# 1-8.net
KiCad netlist of a schematic drawn in EAGLE
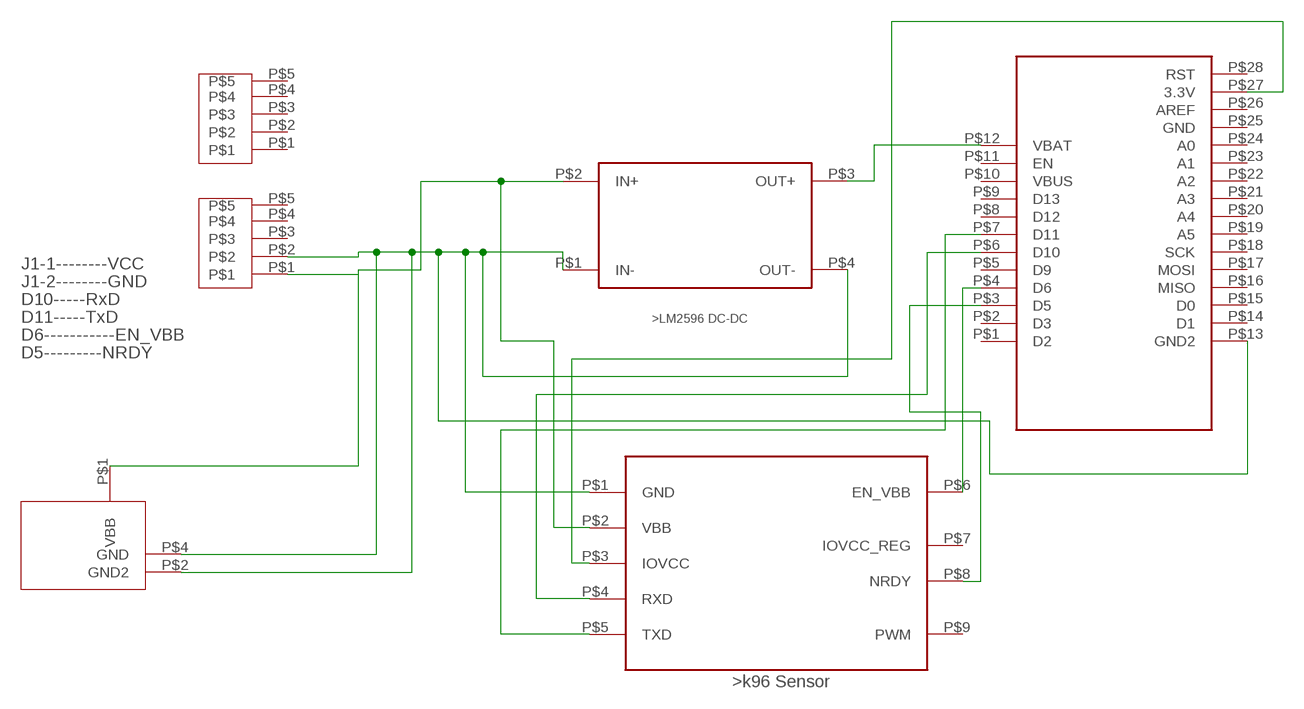
[diagram p0: schematic, sheet 1]

(export (version "E")
  (design (tool "Eeschema 10.0.6"))
  (components
    (comp (ref "DCDC1")
      (value "DCDC")
      (footprint "eagle-import:DCDC")
      (libsource (lib "eagle-import") (part "DCDC"))
    )
    (comp (ref "FEATHER1")
      (value "FEATHER")
      (footprint "eagle-import:FEATHER")
      (libsource (lib "eagle-import") (part "FEATHER"))
    )
    (comp (ref "K96SENSOR1")
      (value "K96SENSOR")
      (footprint "eagle-import:K96SENSOR")
      (libsource (lib "eagle-import") (part "K96SENSOR"))
    )
    (comp (ref "PIN1")
      (value "PIN")
      (footprint "eagle-import:PIN")
      (libsource (lib "eagle-import") (part "PIN"))
    )
    (comp (ref "PIN2")
      (value "PIN")
      (footprint "eagle-import:PIN")
      (libsource (lib "eagle-import") (part "PIN"))
    )
    (comp (ref "U$1")
      (value "POWER")
      (footprint "eagle-import:POWERIN")
      (libsource (lib "eagle-import") (part "POWER"))
    )
  )
  (nets
    (net (code "1") (name "Net-(DCDC1-IN+)") (class "Default")
      (node (ref "DCDC1") (pin "P$2") (pinfunction "IN+_P$2") (pintype "bidirectional"))
      (node (ref "K96SENSOR1") (pin "P$2") (pinfunction "VBB_P$2") (pintype "bidirectional"))
      (node (ref "PIN2") (pin "P$1") (pinfunction "P$1_P$1") (pintype "bidirectional"))
      (node (ref "U$1") (pin "P$1") (pinfunction "VBB_P$1") (pintype "bidirectional"))
    )
    (net (code "2") (name "Net-(DCDC1-IN-)") (class "Default")
      (node (ref "DCDC1") (pin "P$1") (pinfunction "IN-_P$1") (pintype "bidirectional"))
      (node (ref "DCDC1") (pin "P$4") (pinfunction "OUT-_P$4") (pintype "bidirectional"))
      (node (ref "FEATHER1") (pin "P$13") (pinfunction "GND2_P$13") (pintype "bidirectional"))
      (node (ref "K96SENSOR1") (pin "P$1") (pinfunction "GND_P$1") (pintype "bidirectional"))
      (node (ref "PIN2") (pin "P$2") (pinfunction "P$2_P$2") (pintype "bidirectional"))
      (node (ref "U$1") (pin "P$2") (pinfunction "GND2_P$2") (pintype "bidirectional"))
      (node (ref "U$1") (pin "P$4") (pinfunction "GND_P$4") (pintype "bidirectional"))
    )
    (net (code "3") (name "Net-(DCDC1-OUT+)") (class "Default")
      (node (ref "DCDC1") (pin "P$3") (pinfunction "OUT+_P$3") (pintype "bidirectional"))
      (node (ref "FEATHER1") (pin "P$12") (pinfunction "VBAT_P$12") (pintype "bidirectional"))
    )
    (net (code "4") (name "Net-(FEATHER1-3.3V)") (class "Default")
      (node (ref "FEATHER1") (pin "P$27") (pinfunction "3.3V_P$27") (pintype "bidirectional"))
      (node (ref "K96SENSOR1") (pin "P$3") (pinfunction "IOVCC_P$3") (pintype "bidirectional"))
    )
    (net (code "5") (name "Net-(FEATHER1-D5)") (class "Default")
      (node (ref "FEATHER1") (pin "P$3") (pinfunction "D5_P$3") (pintype "bidirectional"))
      (node (ref "K96SENSOR1") (pin "P$8") (pinfunction "NRDY_P$8") (pintype "bidirectional"))
    )
    (net (code "6") (name "Net-(FEATHER1-D6)") (class "Default")
      (node (ref "FEATHER1") (pin "P$4") (pinfunction "D6_P$4") (pintype "bidirectional"))
      (node (ref "K96SENSOR1") (pin "P$6") (pinfunction "EN_VBB_P$6") (pintype "bidirectional"))
    )
    (net (code "7") (name "Net-(FEATHER1-D10)") (class "Default")
      (node (ref "FEATHER1") (pin "P$6") (pinfunction "D10_P$6") (pintype "bidirectional"))
      (node (ref "K96SENSOR1") (pin "P$4") (pinfunction "RXD_P$4") (pintype "bidirectional"))
    )
    (net (code "8") (name "Net-(FEATHER1-D11)") (class "Default")
      (node (ref "FEATHER1") (pin "P$7") (pinfunction "D11_P$7") (pintype "bidirectional"))
      (node (ref "K96SENSOR1") (pin "P$5") (pinfunction "TXD_P$5") (pintype "bidirectional"))
    )
    (net (code "9") (name "unconnected-(FEATHER1-A0-PadP$24)") (class "Default")
      (node (ref "FEATHER1") (pin "P$24") (pinfunction "A0_P$24") (pintype "bidirectional"))
    )
    (net (code "10") (name "unconnected-(FEATHER1-A1-PadP$23)") (class "Default")
      (node (ref "FEATHER1") (pin "P$23") (pinfunction "A1_P$23") (pintype "bidirectional"))
    )
    (net (code "11") (name "unconnected-(FEATHER1-A2-PadP$22)") (class "Default")
      (node (ref "FEATHER1") (pin "P$22") (pinfunction "A2_P$22") (pintype "bidirectional"))
    )
    (net (code "12") (name "unconnected-(FEATHER1-A3-PadP$21)") (class "Default")
      (node (ref "FEATHER1") (pin "P$21") (pinfunction "A3_P$21") (pintype "bidirectional"))
    )
    (net (code "13") (name "unconnected-(FEATHER1-A4-PadP$20)") (class "Default")
      (node (ref "FEATHER1") (pin "P$20") (pinfunction "A4_P$20") (pintype "bidirectional"))
    )
    (net (code "14") (name "unconnected-(FEATHER1-A5-PadP$19)") (class "Default")
      (node (ref "FEATHER1") (pin "P$19") (pinfunction "A5_P$19") (pintype "bidirectional"))
    )
    (net (code "15") (name "unconnected-(FEATHER1-AREF-PadP$26)") (class "Default")
      (node (ref "FEATHER1") (pin "P$26") (pinfunction "AREF_P$26") (pintype "bidirectional"))
    )
    (net (code "16") (name "unconnected-(FEATHER1-D0-PadP$15)") (class "Default")
      (node (ref "FEATHER1") (pin "P$15") (pinfunction "D0_P$15") (pintype "bidirectional"))
    )
    (net (code "17") (name "unconnected-(FEATHER1-D1-PadP$14)") (class "Default")
      (node (ref "FEATHER1") (pin "P$14") (pinfunction "D1_P$14") (pintype "bidirectional"))
    )
    (net (code "18") (name "unconnected-(FEATHER1-D2-PadP$1)") (class "Default")
      (node (ref "FEATHER1") (pin "P$1") (pinfunction "D2_P$1") (pintype "bidirectional"))
    )
    (net (code "19") (name "unconnected-(FEATHER1-D3-PadP$2)") (class "Default")
      (node (ref "FEATHER1") (pin "P$2") (pinfunction "D3_P$2") (pintype "bidirectional"))
    )
    (net (code "20") (name "unconnected-(FEATHER1-D9-PadP$5)") (class "Default")
      (node (ref "FEATHER1") (pin "P$5") (pinfunction "D9_P$5") (pintype "bidirectional"))
    )
    (net (code "21") (name "unconnected-(FEATHER1-D12-PadP$8)") (class "Default")
      (node (ref "FEATHER1") (pin "P$8") (pinfunction "D12_P$8") (pintype "bidirectional"))
    )
    (net (code "22") (name "unconnected-(FEATHER1-D13-PadP$9)") (class "Default")
      (node (ref "FEATHER1") (pin "P$9") (pinfunction "D13_P$9") (pintype "bidirectional"))
    )
    (net (code "23") (name "unconnected-(FEATHER1-EN-PadP$11)") (class "Default")
      (node (ref "FEATHER1") (pin "P$11") (pinfunction "EN_P$11") (pintype "bidirectional"))
    )
    (net (code "24") (name "unconnected-(FEATHER1-GND-PadP$25)") (class "Default")
      (node (ref "FEATHER1") (pin "P$25") (pinfunction "GND_P$25") (pintype "bidirectional"))
    )
    (net (code "25") (name "unconnected-(FEATHER1-MISO-PadP$16)") (class "Default")
      (node (ref "FEATHER1") (pin "P$16") (pinfunction "MISO_P$16") (pintype "bidirectional"))
    )
    (net (code "26") (name "unconnected-(FEATHER1-MOSI-PadP$17)") (class "Default")
      (node (ref "FEATHER1") (pin "P$17") (pinfunction "MOSI_P$17") (pintype "bidirectional"))
    )
    (net (code "27") (name "unconnected-(FEATHER1-RST-PadP$28)") (class "Default")
      (node (ref "FEATHER1") (pin "P$28") (pinfunction "RST_P$28") (pintype "bidirectional"))
    )
    (net (code "28") (name "unconnected-(FEATHER1-SCK-PadP$18)") (class "Default")
      (node (ref "FEATHER1") (pin "P$18") (pinfunction "SCK_P$18") (pintype "bidirectional"))
    )
    (net (code "29") (name "unconnected-(FEATHER1-VBUS-PadP$10)") (class "Default")
      (node (ref "FEATHER1") (pin "P$10") (pinfunction "VBUS_P$10") (pintype "bidirectional"))
    )
    (net (code "30") (name "unconnected-(K96SENSOR1-IOVCC_REG-PadP$7)") (class "Default")
      (node (ref "K96SENSOR1") (pin "P$7") (pinfunction "IOVCC_REG_P$7") (pintype "bidirectional"))
    )
    (net (code "31") (name "unconnected-(K96SENSOR1-PWM-PadP$9)") (class "Default")
      (node (ref "K96SENSOR1") (pin "P$9") (pinfunction "PWM_P$9") (pintype "bidirectional"))
    )
    (net (code "32") (name "unconnected-(PIN1-PadP$1)") (class "Default")
      (node (ref "PIN1") (pin "P$1") (pinfunction "P$1_P$1") (pintype "bidirectional"))
    )
    (net (code "33") (name "unconnected-(PIN1-PadP$2)") (class "Default")
      (node (ref "PIN1") (pin "P$2") (pinfunction "P$2_P$2") (pintype "bidirectional"))
    )
    (net (code "34") (name "unconnected-(PIN1-PadP$3)") (class "Default")
      (node (ref "PIN1") (pin "P$3") (pinfunction "P$3_P$3") (pintype "bidirectional"))
    )
    (net (code "35") (name "unconnected-(PIN1-PadP$4)") (class "Default")
      (node (ref "PIN1") (pin "P$4") (pinfunction "P$4_P$4") (pintype "bidirectional"))
    )
    (net (code "36") (name "unconnected-(PIN1-PadP$5)") (class "Default")
      (node (ref "PIN1") (pin "P$5") (pinfunction "P$5_P$5") (pintype "bidirectional"))
    )
    (net (code "37") (name "unconnected-(PIN2-PadP$3)") (class "Default")
      (node (ref "PIN2") (pin "P$3") (pinfunction "P$3_P$3") (pintype "bidirectional"))
    )
    (net (code "38") (name "unconnected-(PIN2-PadP$4)") (class "Default")
      (node (ref "PIN2") (pin "P$4") (pinfunction "P$4_P$4") (pintype "bidirectional"))
    )
    (net (code "39") (name "unconnected-(PIN2-PadP$5)") (class "Default")
      (node (ref "PIN2") (pin "P$5") (pinfunction "P$5_P$5") (pintype "bidirectional"))
    )
  )
)
